# TestBoardRevA.net
KiCad netlist of a schematic drawn in EAGLE
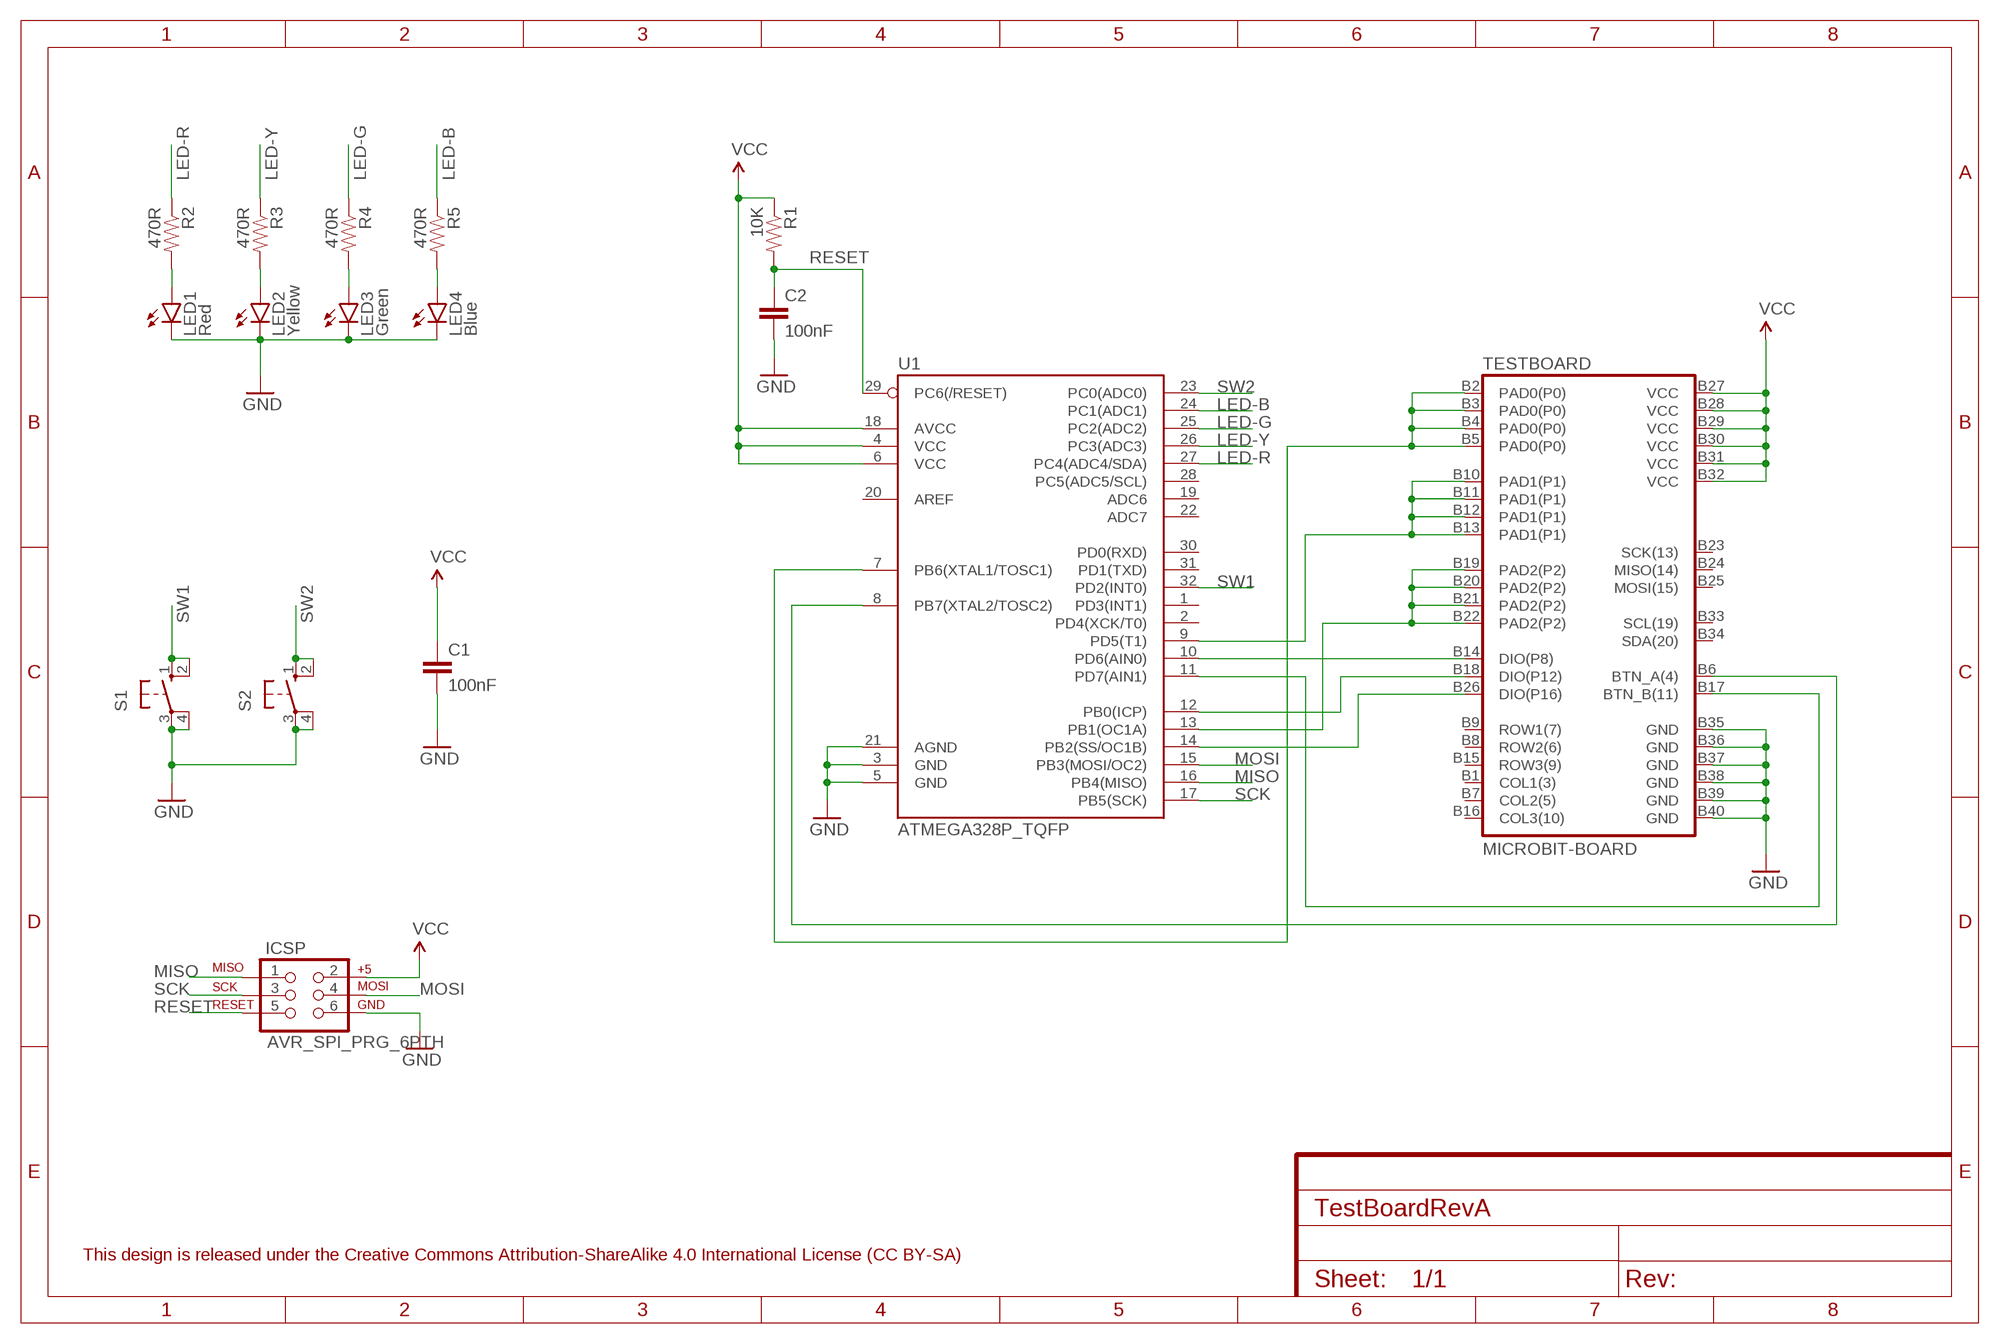
[diagram p0: schematic, sheet 1]

(export (version "E")
  (design (tool "Eeschema 10.0.6"))
  (components
    (comp (ref "C1")
      (value "100nF")
      (footprint "eagle-import:0603-CAP")
      (libsource (lib "eagle-import") (part "CAP0603-CAP"))
    )
    (comp (ref "C2")
      (value "100nF")
      (footprint "eagle-import:0603-CAP")
      (libsource (lib "eagle-import") (part "CAP0603-CAP"))
    )
    (comp (ref "ICSP")
      (value "AVR_SPI_PRG_6PTH")
      (footprint "eagle-import:2X3")
      (libsource (lib "eagle-import") (part "AVR_SPI_PRG_6PTH"))
    )
    (comp (ref "LED1")
      (value "Red")
      (footprint "eagle-import:LED-0603")
      (libsource (lib "eagle-import") (part "LED0603"))
    )
    (comp (ref "LED2")
      (value "Yellow")
      (footprint "eagle-import:LED-0603")
      (libsource (lib "eagle-import") (part "LED0603"))
    )
    (comp (ref "LED3")
      (value "Green")
      (footprint "eagle-import:LED-0603")
      (libsource (lib "eagle-import") (part "LED0603"))
    )
    (comp (ref "LED4")
      (value "Blue")
      (footprint "eagle-import:LED-0603")
      (libsource (lib "eagle-import") (part "LED0603"))
    )
    (comp (ref "R1")
      (value "10K")
      (footprint "eagle-import:0603-RES")
      (libsource (lib "eagle-import") (part "RESISTOR0603-RES"))
    )
    (comp (ref "R2")
      (value "470R")
      (footprint "eagle-import:0603-RES")
      (libsource (lib "eagle-import") (part "RESISTOR0603-RES"))
    )
    (comp (ref "R3")
      (value "470R")
      (footprint "eagle-import:0603-RES")
      (libsource (lib "eagle-import") (part "RESISTOR0603-RES"))
    )
    (comp (ref "R4")
      (value "470R")
      (footprint "eagle-import:0603-RES")
      (libsource (lib "eagle-import") (part "RESISTOR0603-RES"))
    )
    (comp (ref "R5")
      (value "470R")
      (footprint "eagle-import:0603-RES")
      (libsource (lib "eagle-import") (part "RESISTOR0603-RES"))
    )
    (comp (ref "S1")
      (value "10-XX")
      (footprint "eagle-import:B3F-10XX")
      (fields (field (name "MPN") "B3F-1000"))
      (libsource (lib "eagle-import") (part "10-XX"))
    )
    (comp (ref "S2")
      (value "10-XX")
      (footprint "eagle-import:B3F-10XX")
      (fields (field (name "MPN") "B3F-1000"))
      (libsource (lib "eagle-import") (part "10-XX"))
    )
    (comp (ref "TESTBOARD")
      (value "MICROBIT-BOARD")
      (footprint "eagle-import:MICROBIT-EDGE-CONN")
      (libsource (lib "eagle-import") (part "MICROBIT-BOARD"))
    )
    (comp (ref "U1")
      (value "ATMEGA328P_TQFP")
      (footprint "eagle-import:TQFP32-08")
      (libsource (lib "eagle-import") (part "ATMEGA328P_TQFP"))
    )
  )
  (nets
    (net (code "1") (name "/LED-B") (class "Default")
      (node (ref "R5") (pin "1") (pinfunction "1_1") (pintype "passive"))
      (node (ref "U1") (pin "24") (pinfunction "PC1(ADC1)_24") (pintype "bidirectional"))
    )
    (net (code "2") (name "/LED-G") (class "Default")
      (node (ref "R4") (pin "1") (pinfunction "1_1") (pintype "passive"))
      (node (ref "U1") (pin "25") (pinfunction "PC2(ADC2)_25") (pintype "bidirectional"))
    )
    (net (code "3") (name "/LED-R") (class "Default")
      (node (ref "R2") (pin "1") (pinfunction "1_1") (pintype "passive"))
      (node (ref "U1") (pin "27") (pinfunction "PC4(ADC4/SDA)_27") (pintype "bidirectional"))
    )
    (net (code "4") (name "/LED-Y") (class "Default")
      (node (ref "R3") (pin "1") (pinfunction "1_1") (pintype "passive"))
      (node (ref "U1") (pin "26") (pinfunction "PC3(ADC3)_26") (pintype "bidirectional"))
    )
    (net (code "5") (name "/MISO") (class "Default")
      (node (ref "ICSP") (pin "1") (pinfunction "1_1") (pintype "passive"))
      (node (ref "U1") (pin "16") (pinfunction "PB4(MISO)_16") (pintype "bidirectional"))
    )
    (net (code "6") (name "/MOSI") (class "Default")
      (node (ref "ICSP") (pin "4") (pinfunction "4_4") (pintype "passive"))
      (node (ref "U1") (pin "15") (pinfunction "PB3(MOSI/OC2)_15") (pintype "bidirectional"))
    )
    (net (code "7") (name "/RESET") (class "Default")
      (node (ref "C2") (pin "1") (pinfunction "1_1") (pintype "passive"))
      (node (ref "ICSP") (pin "5") (pinfunction "5_5") (pintype "passive"))
      (node (ref "R1") (pin "2") (pinfunction "2_2") (pintype "passive"))
      (node (ref "U1") (pin "29") (pinfunction "PC6(/RESET)_29") (pintype "bidirectional"))
    )
    (net (code "8") (name "/SCK") (class "Default")
      (node (ref "ICSP") (pin "3") (pinfunction "3_3") (pintype "passive"))
      (node (ref "U1") (pin "17") (pinfunction "PB5(SCK)_17") (pintype "bidirectional"))
    )
    (net (code "9") (name "/SW1") (class "Default")
      (node (ref "S1") (pin "1") (pinfunction "S_1") (pintype "passive"))
      (node (ref "S1") (pin "2") (pinfunction "S1_2") (pintype "passive"))
      (node (ref "U1") (pin "32") (pinfunction "PD2(INT0)_32") (pintype "bidirectional"))
    )
    (net (code "10") (name "/SW2") (class "Default")
      (node (ref "S2") (pin "1") (pinfunction "S_1") (pintype "passive"))
      (node (ref "S2") (pin "2") (pinfunction "S1_2") (pintype "passive"))
      (node (ref "U1") (pin "23") (pinfunction "PC0(ADC0)_23") (pintype "bidirectional"))
    )
    (net (code "11") (name "GND") (class "Default")
      (node (ref "C1") (pin "2") (pinfunction "2_2") (pintype "passive"))
      (node (ref "C2") (pin "2") (pinfunction "2_2") (pintype "passive"))
      (node (ref "ICSP") (pin "6") (pinfunction "6_6") (pintype "passive"))
      (node (ref "LED1") (pin "C") (pinfunction "C_C") (pintype "passive"))
      (node (ref "LED2") (pin "C") (pinfunction "C_C") (pintype "passive"))
      (node (ref "LED3") (pin "C") (pinfunction "C_C") (pintype "passive"))
      (node (ref "LED4") (pin "C") (pinfunction "C_C") (pintype "passive"))
      (node (ref "S1") (pin "3") (pinfunction "P_3") (pintype "passive"))
      (node (ref "S1") (pin "4") (pinfunction "P1_4") (pintype "passive"))
      (node (ref "S2") (pin "3") (pinfunction "P_3") (pintype "passive"))
      (node (ref "S2") (pin "4") (pinfunction "P1_4") (pintype "passive"))
      (node (ref "TESTBOARD") (pin "B35") (pinfunction "GND_B35") (pintype "power_in"))
      (node (ref "TESTBOARD") (pin "B36") (pinfunction "GND_B36") (pintype "power_in"))
      (node (ref "TESTBOARD") (pin "B37") (pinfunction "GND_B37") (pintype "power_in"))
      (node (ref "TESTBOARD") (pin "B38") (pinfunction "GND_B38") (pintype "power_in"))
      (node (ref "TESTBOARD") (pin "B39") (pinfunction "GND_B39") (pintype "power_in"))
      (node (ref "TESTBOARD") (pin "B40") (pinfunction "GND_B40") (pintype "power_in"))
      (node (ref "U1") (pin "21") (pinfunction "AGND_21") (pintype "bidirectional"))
      (node (ref "U1") (pin "3") (pinfunction "GND_3") (pintype "bidirectional"))
      (node (ref "U1") (pin "5") (pinfunction "GND_5") (pintype "bidirectional"))
    )
    (net (code "12") (name "Net-(LED1-PadA)") (class "Default")
      (node (ref "LED1") (pin "A") (pinfunction "A_A") (pintype "passive"))
      (node (ref "R2") (pin "2") (pinfunction "2_2") (pintype "passive"))
    )
    (net (code "13") (name "Net-(LED2-PadA)") (class "Default")
      (node (ref "LED2") (pin "A") (pinfunction "A_A") (pintype "passive"))
      (node (ref "R3") (pin "2") (pinfunction "2_2") (pintype "passive"))
    )
    (net (code "14") (name "Net-(LED3-PadA)") (class "Default")
      (node (ref "LED3") (pin "A") (pinfunction "A_A") (pintype "passive"))
      (node (ref "R4") (pin "2") (pinfunction "2_2") (pintype "passive"))
    )
    (net (code "15") (name "Net-(LED4-PadA)") (class "Default")
      (node (ref "LED4") (pin "A") (pinfunction "A_A") (pintype "passive"))
      (node (ref "R5") (pin "2") (pinfunction "2_2") (pintype "passive"))
    )
    (net (code "16") (name "Net-(TESTBOARD-BTN_A(4))") (class "Default")
      (node (ref "TESTBOARD") (pin "B6") (pinfunction "BTN_A(4)_B6") (pintype "input"))
      (node (ref "U1") (pin "8") (pinfunction "PB7(XTAL2/TOSC2)_8") (pintype "bidirectional"))
    )
    (net (code "17") (name "Net-(TESTBOARD-BTN_B(11))") (class "Default")
      (node (ref "TESTBOARD") (pin "B17") (pinfunction "BTN_B(11)_B17") (pintype "input"))
      (node (ref "U1") (pin "11") (pinfunction "PD7(AIN1)_11") (pintype "bidirectional"))
    )
    (net (code "18") (name "Net-(TESTBOARD-DIO(P8))") (class "Default")
      (node (ref "TESTBOARD") (pin "B14") (pinfunction "DIO(P8)_B14") (pintype "bidirectional"))
      (node (ref "U1") (pin "10") (pinfunction "PD6(AIN0)_10") (pintype "bidirectional"))
    )
    (net (code "19") (name "Net-(TESTBOARD-DIO(P12))") (class "Default")
      (node (ref "TESTBOARD") (pin "B18") (pinfunction "DIO(P12)_B18") (pintype "bidirectional"))
      (node (ref "U1") (pin "12") (pinfunction "PB0(ICP)_12") (pintype "bidirectional"))
    )
    (net (code "20") (name "Net-(TESTBOARD-DIO(P16))") (class "Default")
      (node (ref "TESTBOARD") (pin "B26") (pinfunction "DIO(P16)_B26") (pintype "bidirectional"))
      (node (ref "U1") (pin "14") (pinfunction "PB2(SS/OC1B)_14") (pintype "bidirectional"))
    )
    (net (code "21") (name "Net-(U1-PB1(OC1A))") (class "Default")
      (node (ref "TESTBOARD") (pin "B19") (pinfunction "PAD2(P2)_B19") (pintype "bidirectional"))
      (node (ref "TESTBOARD") (pin "B20") (pinfunction "PAD2(P2)_B20") (pintype "bidirectional"))
      (node (ref "TESTBOARD") (pin "B21") (pinfunction "PAD2(P2)_B21") (pintype "bidirectional"))
      (node (ref "TESTBOARD") (pin "B22") (pinfunction "PAD2(P2)_B22") (pintype "bidirectional"))
      (node (ref "U1") (pin "13") (pinfunction "PB1(OC1A)_13") (pintype "bidirectional"))
    )
    (net (code "22") (name "Net-(U1-PB6(XTAL1{slash}TOSC1))") (class "Default")
      (node (ref "TESTBOARD") (pin "B2") (pinfunction "PAD0(P0)_B2") (pintype "bidirectional"))
      (node (ref "TESTBOARD") (pin "B3") (pinfunction "PAD0(P0)_B3") (pintype "bidirectional"))
      (node (ref "TESTBOARD") (pin "B4") (pinfunction "PAD0(P0)_B4") (pintype "bidirectional"))
      (node (ref "TESTBOARD") (pin "B5") (pinfunction "PAD0(P0)_B5") (pintype "bidirectional"))
      (node (ref "U1") (pin "7") (pinfunction "PB6(XTAL1/TOSC1)_7") (pintype "bidirectional"))
    )
    (net (code "23") (name "Net-(U1-PD5(T1))") (class "Default")
      (node (ref "TESTBOARD") (pin "B10") (pinfunction "PAD1(P1)_B10") (pintype "bidirectional"))
      (node (ref "TESTBOARD") (pin "B11") (pinfunction "PAD1(P1)_B11") (pintype "bidirectional"))
      (node (ref "TESTBOARD") (pin "B12") (pinfunction "PAD1(P1)_B12") (pintype "bidirectional"))
      (node (ref "TESTBOARD") (pin "B13") (pinfunction "PAD1(P1)_B13") (pintype "bidirectional"))
      (node (ref "U1") (pin "9") (pinfunction "PD5(T1)_9") (pintype "bidirectional"))
    )
    (net (code "24") (name "VCC") (class "Default")
      (node (ref "C1") (pin "1") (pinfunction "1_1") (pintype "passive"))
      (node (ref "ICSP") (pin "2") (pinfunction "2_2") (pintype "passive"))
      (node (ref "R1") (pin "1") (pinfunction "1_1") (pintype "passive"))
      (node (ref "TESTBOARD") (pin "B27") (pinfunction "VCC_B27") (pintype "power_in"))
      (node (ref "TESTBOARD") (pin "B28") (pinfunction "VCC_B28") (pintype "power_in"))
      (node (ref "TESTBOARD") (pin "B29") (pinfunction "VCC_B29") (pintype "power_in"))
      (node (ref "TESTBOARD") (pin "B30") (pinfunction "VCC_B30") (pintype "power_in"))
      (node (ref "TESTBOARD") (pin "B31") (pinfunction "VCC_B31") (pintype "power_in"))
      (node (ref "TESTBOARD") (pin "B32") (pinfunction "VCC_B32") (pintype "power_in"))
      (node (ref "U1") (pin "18") (pinfunction "AVCC_18") (pintype "bidirectional"))
      (node (ref "U1") (pin "4") (pinfunction "VCC_4") (pintype "bidirectional"))
      (node (ref "U1") (pin "6") (pinfunction "VCC_6") (pintype "bidirectional"))
    )
    (net (code "25") (name "unconnected-(TESTBOARD-COL1(3)-PadB1)") (class "Default")
      (node (ref "TESTBOARD") (pin "B1") (pinfunction "COL1(3)_B1") (pintype "output"))
    )
    (net (code "26") (name "unconnected-(TESTBOARD-COL2(5)-PadB7)") (class "Default")
      (node (ref "TESTBOARD") (pin "B7") (pinfunction "COL2(5)_B7") (pintype "output"))
    )
    (net (code "27") (name "unconnected-(TESTBOARD-COL3(10)-PadB16)") (class "Default")
      (node (ref "TESTBOARD") (pin "B16") (pinfunction "COL3(10)_B16") (pintype "output"))
    )
    (net (code "28") (name "unconnected-(TESTBOARD-MISO(14)-PadB24)") (class "Default")
      (node (ref "TESTBOARD") (pin "B24") (pinfunction "MISO(14)_B24") (pintype "bidirectional"))
    )
    (net (code "29") (name "unconnected-(TESTBOARD-MOSI(15)-PadB25)") (class "Default")
      (node (ref "TESTBOARD") (pin "B25") (pinfunction "MOSI(15)_B25") (pintype "bidirectional"))
    )
    (net (code "30") (name "unconnected-(TESTBOARD-ROW1(7)-PadB9)") (class "Default")
      (node (ref "TESTBOARD") (pin "B9") (pinfunction "ROW1(7)_B9") (pintype "output"))
    )
    (net (code "31") (name "unconnected-(TESTBOARD-ROW2(6)-PadB8)") (class "Default")
      (node (ref "TESTBOARD") (pin "B8") (pinfunction "ROW2(6)_B8") (pintype "output"))
    )
    (net (code "32") (name "unconnected-(TESTBOARD-ROW3(9)-PadB15)") (class "Default")
      (node (ref "TESTBOARD") (pin "B15") (pinfunction "ROW3(9)_B15") (pintype "output"))
    )
    (net (code "33") (name "unconnected-(TESTBOARD-SCK(13)-PadB23)") (class "Default")
      (node (ref "TESTBOARD") (pin "B23") (pinfunction "SCK(13)_B23") (pintype "bidirectional"))
    )
    (net (code "34") (name "unconnected-(TESTBOARD-SCL(19)-PadB33)") (class "Default")
      (node (ref "TESTBOARD") (pin "B33") (pinfunction "SCL(19)_B33") (pintype "bidirectional"))
    )
    (net (code "35") (name "unconnected-(TESTBOARD-SDA(20)-PadB34)") (class "Default")
      (node (ref "TESTBOARD") (pin "B34") (pinfunction "SDA(20)_B34") (pintype "bidirectional"))
    )
    (net (code "36") (name "unconnected-(U1-ADC6-Pad19)") (class "Default")
      (node (ref "U1") (pin "19") (pinfunction "ADC6_19") (pintype "bidirectional"))
    )
    (net (code "37") (name "unconnected-(U1-ADC7-Pad22)") (class "Default")
      (node (ref "U1") (pin "22") (pinfunction "ADC7_22") (pintype "bidirectional"))
    )
    (net (code "38") (name "unconnected-(U1-AREF-Pad20)") (class "Default")
      (node (ref "U1") (pin "20") (pinfunction "AREF_20") (pintype "bidirectional"))
    )
    (net (code "39") (name "unconnected-(U1-PC5(ADC5{slash}SCL)-Pad28)") (class "Default")
      (node (ref "U1") (pin "28") (pinfunction "PC5(ADC5/SCL)_28") (pintype "bidirectional"))
    )
    (net (code "40") (name "unconnected-(U1-PD0(RXD)-Pad30)") (class "Default")
      (node (ref "U1") (pin "30") (pinfunction "PD0(RXD)_30") (pintype "bidirectional"))
    )
    (net (code "41") (name "unconnected-(U1-PD1(TXD)-Pad31)") (class "Default")
      (node (ref "U1") (pin "31") (pinfunction "PD1(TXD)_31") (pintype "bidirectional"))
    )
    (net (code "42") (name "unconnected-(U1-PD3(INT1)-Pad1)") (class "Default")
      (node (ref "U1") (pin "1") (pinfunction "PD3(INT1)_1") (pintype "bidirectional"))
    )
    (net (code "43") (name "unconnected-(U1-PD4(XCK{slash}T0)-Pad2)") (class "Default")
      (node (ref "U1") (pin "2") (pinfunction "PD4(XCK/T0)_2") (pintype "bidirectional"))
    )
  )
)
